# 07_MT7688AN_RF_Front_End.net
KiCad netlist of a schematic drawn in Altium Designer
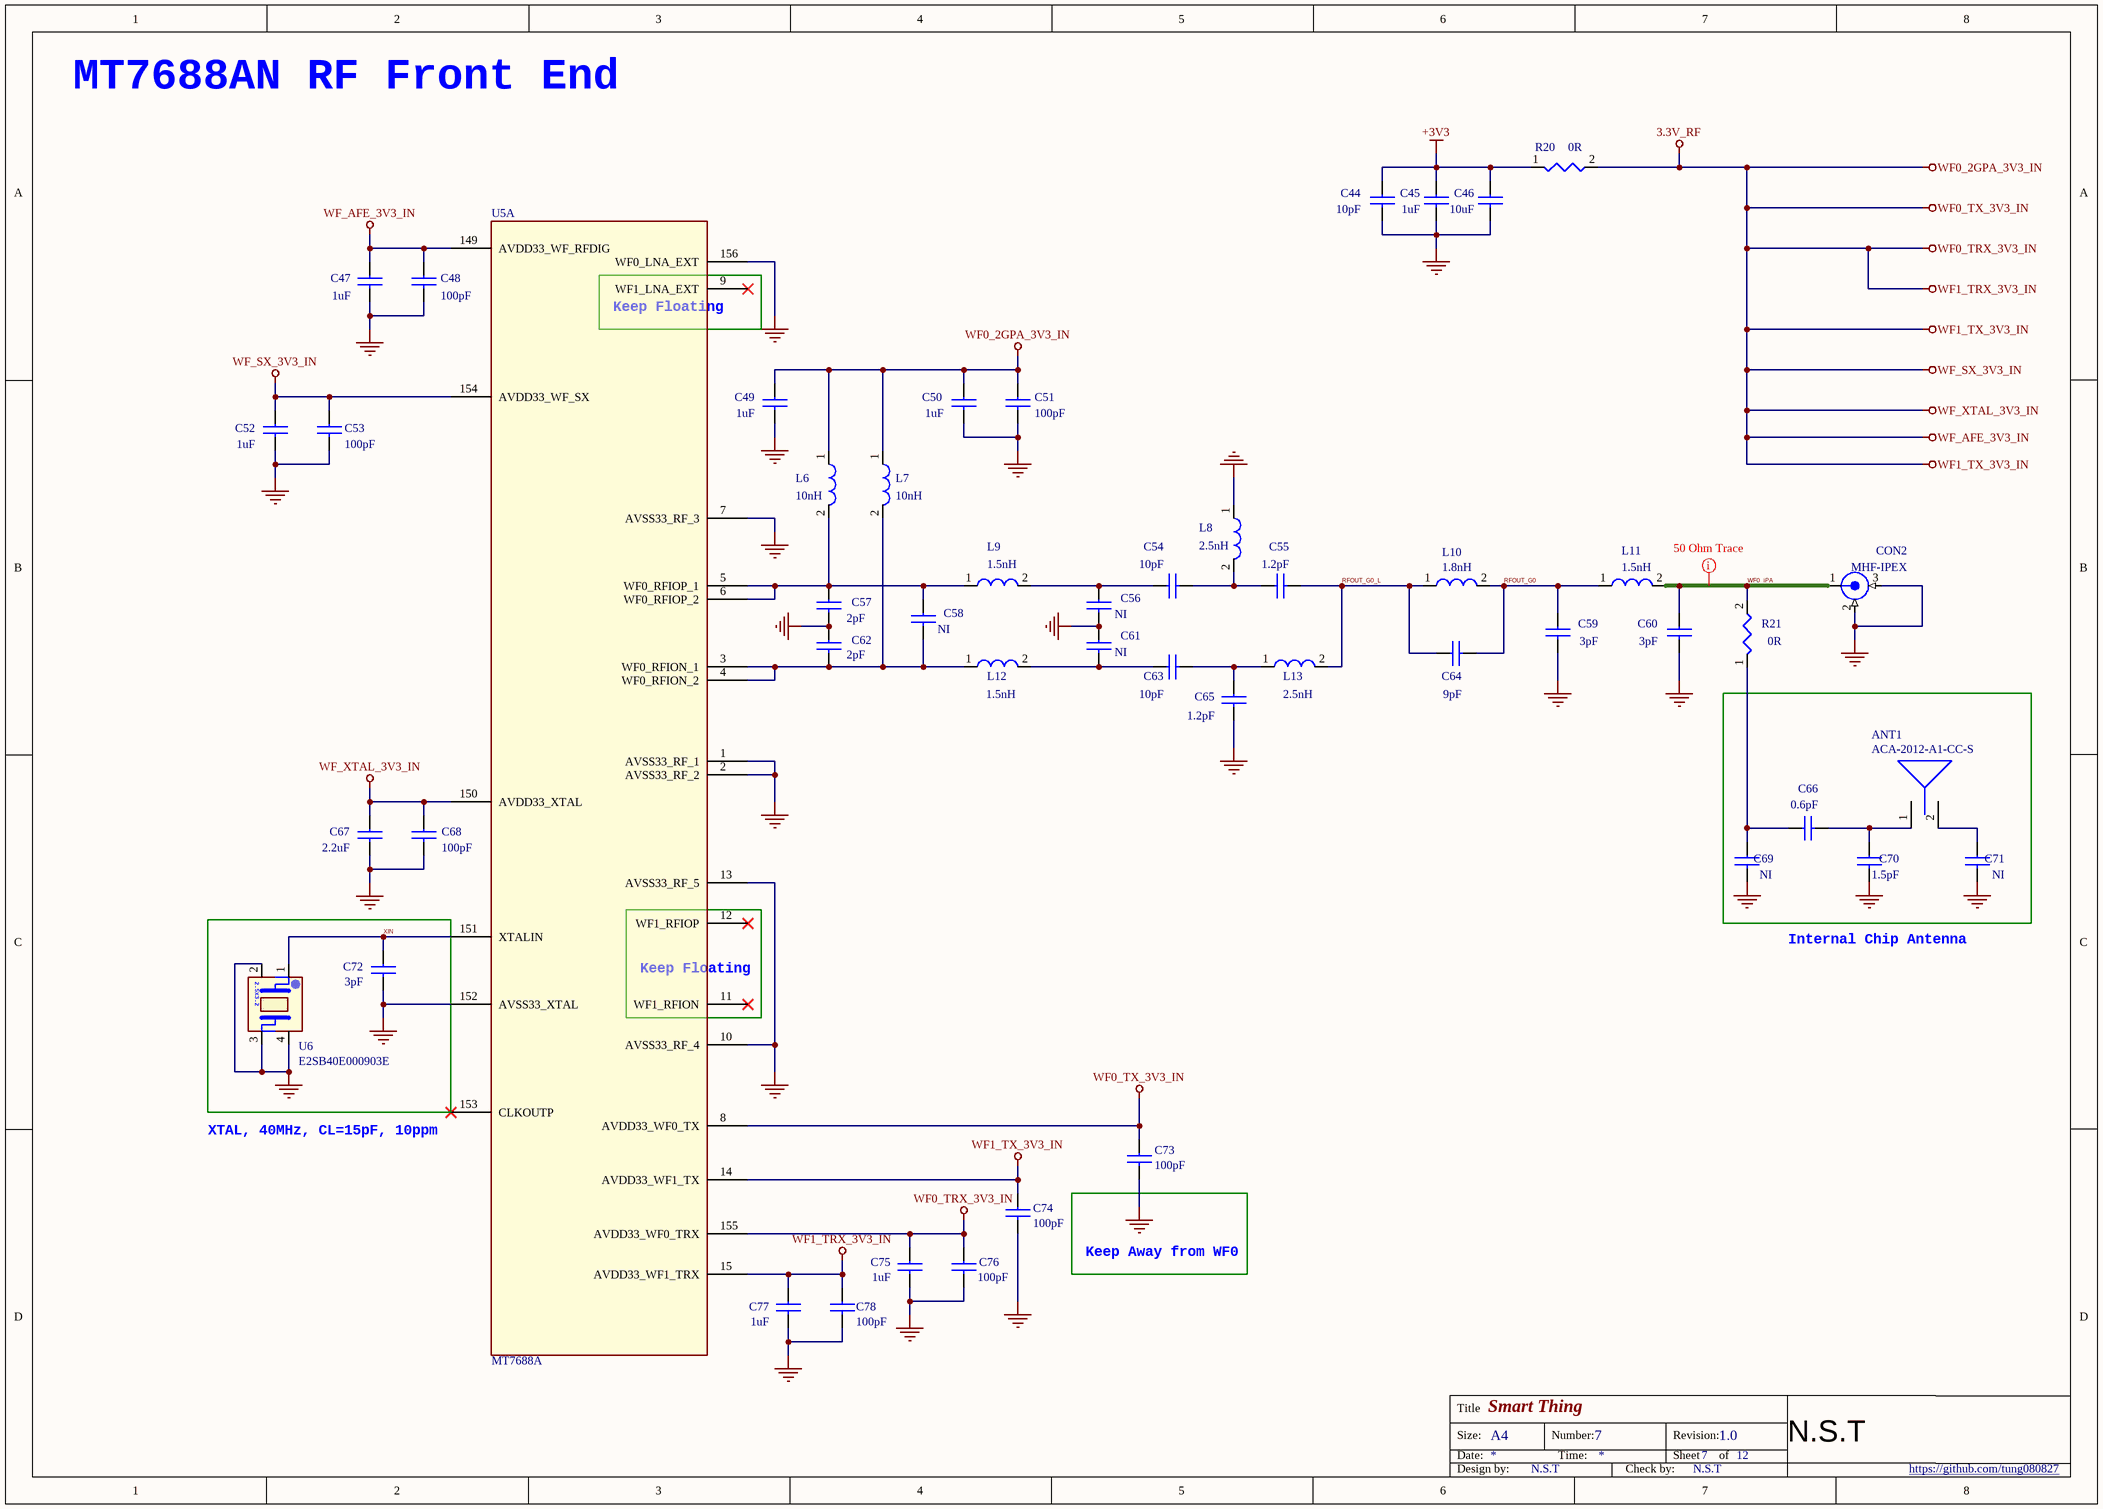
[diagram p0: 07. MT7688AN RF Front End.SchDoc]

(export (version "E")
  (design (tool "Eeschema 10.0.6"))
  (components
    (comp (ref "ANT1")
      (value "ACA-2012-A1-CC-S")
      (footprint "ACA-2012A")
      (libsource (lib "MT7688AN") (part "Antenna_2012"))
    )
    (comp (ref "C44")
      (value "10pF")
      (footprint "CAPC1005X60X30NL05T10")
      (libsource (lib "MT7688AN") (part "CAP NP"))
    )
    (comp (ref "C45")
      (value "1uF")
      (footprint "CAPC1608X90X35NL10T15")
      (libsource (lib "MT7688AN") (part "CAP NP"))
    )
    (comp (ref "C46")
      (value "10uF")
      (footprint "CAPC1608X90X35NL10T15")
      (libsource (lib "MT7688AN") (part "CAP NP"))
    )
    (comp (ref "C47")
      (value "1uF")
      (footprint "CAPC1608X90X35NL10T15")
      (libsource (lib "MT7688AN") (part "CAP NP"))
    )
    (comp (ref "C48")
      (value "100pF")
      (footprint "CAPC1005X60X30NL05T10")
      (libsource (lib "MT7688AN") (part "CAP NP"))
    )
    (comp (ref "C49")
      (value "1uF")
      (footprint "CAPC1005X60X30NL05T10")
      (libsource (lib "MT7688AN") (part "CAP NP"))
    )
    (comp (ref "C50")
      (value "1uF")
      (footprint "CAPC1005X60X30NL05T10")
      (libsource (lib "MT7688AN") (part "CAP NP"))
    )
    (comp (ref "C51")
      (value "100pF")
      (footprint "CAPC1005X60X30NL05T10")
      (libsource (lib "MT7688AN") (part "CAP NP"))
    )
    (comp (ref "C52")
      (value "1uF")
      (footprint "CAPC1608X90X35NL10T15")
      (libsource (lib "MT7688AN") (part "CAP NP"))
    )
    (comp (ref "C53")
      (value "100pF")
      (footprint "CAPC1005X60X30NL05T10")
      (libsource (lib "MT7688AN") (part "CAP NP"))
    )
    (comp (ref "C54")
      (value "10pF")
      (footprint "CAPC1005X60X30NL05T10")
      (libsource (lib "MT7688AN") (part "CAP NP"))
    )
    (comp (ref "C55")
      (value "1.2pF")
      (footprint "CAPC1005X60X30NL05T10")
      (libsource (lib "MT7688AN") (part "CAP NP"))
    )
    (comp (ref "C56")
      (value "NI")
      (footprint "CAPC1005X60X30NL05T10")
      (libsource (lib "MT7688AN") (part "CAP NP"))
    )
    (comp (ref "C57")
      (value "2pF")
      (footprint "CAPC1005X60X30NL05T10")
      (libsource (lib "MT7688AN") (part "CAP NP"))
    )
    (comp (ref "C58")
      (value "NI")
      (footprint "CAPC1005X60X30NL05T10")
      (libsource (lib "MT7688AN") (part "CAP NP"))
    )
    (comp (ref "C59")
      (value "3pF")
      (footprint "CAPC1005X60X30NL05T10")
      (libsource (lib "MT7688AN") (part "CAP NP"))
    )
    (comp (ref "C60")
      (value "3pF")
      (footprint "CAPC1005X60X30NL05T10")
      (libsource (lib "MT7688AN") (part "CAP NP"))
    )
    (comp (ref "C61")
      (value "NI")
      (footprint "CAPC1005X60X30NL05T10")
      (libsource (lib "MT7688AN") (part "CAP NP"))
    )
    (comp (ref "C62")
      (value "2pF")
      (footprint "CAPC1005X60X30NL05T10")
      (libsource (lib "MT7688AN") (part "CAP NP"))
    )
    (comp (ref "C63")
      (value "10pF")
      (footprint "CAPC1005X60X30NL05T10")
      (libsource (lib "MT7688AN") (part "CAP NP"))
    )
    (comp (ref "C64")
      (value "9pF")
      (footprint "CAPC1005X60X30NL05T10")
      (libsource (lib "MT7688AN") (part "CAP NP"))
    )
    (comp (ref "C65")
      (value "1.2pF")
      (footprint "CAPC1005X60X30NL05T10")
      (libsource (lib "MT7688AN") (part "CAP NP"))
    )
    (comp (ref "C66")
      (value "0.6pF")
      (footprint "CAPC1005X60X30NL05T10")
      (libsource (lib "MT7688AN") (part "CAP NP"))
    )
    (comp (ref "C67")
      (value "2.2uF")
      (footprint "CAPC1608X90X35NL10T15")
      (libsource (lib "MT7688AN") (part "CAP NP"))
    )
    (comp (ref "C68")
      (value "100pF")
      (footprint "CAPC1005X60X30NL05T10")
      (libsource (lib "MT7688AN") (part "CAP NP"))
    )
    (comp (ref "C69")
      (value "NI")
      (footprint "CAPC1005X60X30NL05T10")
      (libsource (lib "MT7688AN") (part "CAP NP"))
    )
    (comp (ref "C70")
      (value "1.5pF")
      (footprint "CAPC1005X60X30NL05T10")
      (libsource (lib "MT7688AN") (part "CAP NP"))
    )
    (comp (ref "C71")
      (value "NI")
      (footprint "CAPC1005X60X30NL05T10")
      (libsource (lib "MT7688AN") (part "CAP NP"))
    )
    (comp (ref "C72")
      (value "3pF")
      (footprint "CAPC1005X60X30NL05T10")
      (libsource (lib "MT7688AN") (part "CAP NP"))
    )
    (comp (ref "C73")
      (value "100pF")
      (footprint "CAPC1005X60X30NL05T10")
      (libsource (lib "MT7688AN") (part "CAP NP"))
    )
    (comp (ref "C74")
      (value "100pF")
      (footprint "CAPC1005X60X30NL05T10")
      (libsource (lib "MT7688AN") (part "CAP NP"))
    )
    (comp (ref "C75")
      (value "1uF")
      (footprint "CAPC1608X90X35NL10T15")
      (libsource (lib "MT7688AN") (part "CAP NP"))
    )
    (comp (ref "C76")
      (value "100pF")
      (footprint "CAPC1005X60X30NL05T10")
      (libsource (lib "MT7688AN") (part "CAP NP"))
    )
    (comp (ref "C77")
      (value "1uF")
      (footprint "CAPC1608X90X35NL10T15")
      (libsource (lib "MT7688AN") (part "CAP NP"))
    )
    (comp (ref "C78")
      (value "100pF")
      (footprint "CAPC1005X60X30NL05T10")
      (libsource (lib "MT7688AN") (part "CAP NP"))
    )
    (comp (ref "CON2")
      (value "MHF-IPEX")
      (footprint "I-PEX CON")
      (libsource (lib "MT7688AN") (part "SMA/UFLR"))
    )
    (comp (ref "L6")
      (value "10nH")
      (footprint "CAPC1005X60X30NL05T10")
      (libsource (lib "MT7688AN") (part "L/0402"))
    )
    (comp (ref "L7")
      (value "10nH")
      (footprint "CAPC1005X60X30NL05T10")
      (libsource (lib "MT7688AN") (part "L/0402"))
    )
    (comp (ref "L8")
      (value "2.5nH")
      (footprint "CAPC1005X60X30NL05T10")
      (libsource (lib "MT7688AN") (part "L/0402"))
    )
    (comp (ref "L9")
      (value "1.5nH")
      (footprint "CAPC1005X60X30NL05T10")
      (description "LQP03TN1N5B02D")
      (libsource (lib "MT7688AN") (part "L/0402"))
    )
    (comp (ref "L10")
      (value "1.8nH")
      (footprint "CAPC1005X60X30NL05T10")
      (libsource (lib "MT7688AN") (part "L/0402"))
    )
    (comp (ref "L11")
      (value "1.5nH")
      (footprint "CAPC1005X60X30NL05T10")
      (description "LQP03TN1N5B02D")
      (libsource (lib "MT7688AN") (part "L/0402"))
    )
    (comp (ref "L12")
      (value "1.5nH")
      (footprint "CAPC1005X60X30NL05T10")
      (description "LQP03TN1N5B02D")
      (libsource (lib "MT7688AN") (part "L/0402"))
    )
    (comp (ref "L13")
      (value "2.5nH")
      (footprint "CAPC1005X60X30NL05T10")
      (libsource (lib "MT7688AN") (part "L/0402"))
    )
    (comp (ref "R20")
      (value "0R")
      (footprint "RESC1609X50X30LL10T20")
      (libsource (lib "MT7688AN") (part "RES/0402_3"))
    )
    (comp (ref "R21")
      (value "0R")
      (footprint "RESC1005X40X25NL05T05")
      (libsource (lib "MT7688AN") (part "RES/0402_3"))
    )
    (comp (ref "U5")
      (value "MT7688A")
      (footprint "MT7628AN12X12")
      (libsource (lib "MT7688AN") (part "MT7620N-n_26"))
    )
    (comp (ref "U6")
      (value "E2SB40E000903E")
      (footprint "XTAL 2520")
      (description "XTAL, 40MHz, CL=15pF, 10ppm, -30~+85C")
      (libsource (lib "MT7688AN") (part "XTAL_3.2x2.5"))
    )
  )
  (nets
    (net (code "1") (name "+3V3") (class "Default")
      (node (ref "C44") (pin "1") (pinfunction "1_1") (pintype "passive"))
      (node (ref "C45") (pin "1") (pinfunction "1_1") (pintype "passive"))
      (node (ref "C46") (pin "1") (pinfunction "1_1") (pintype "passive"))
      (node (ref "R20") (pin "1") (pinfunction "1_1") (pintype "passive"))
    )
    (net (code "2") (name "/RFOUT_G0") (class "Default")
      (node (ref "C59") (pin "1") (pinfunction "1_1") (pintype "passive"))
      (node (ref "C64") (pin "2") (pinfunction "2_2") (pintype "passive"))
      (node (ref "L10") (pin "2") (pinfunction "2_2") (pintype "passive"))
      (node (ref "L11") (pin "1") (pinfunction "1_1") (pintype "passive"))
    )
    (net (code "3") (name "/RFOUT_G0_L") (class "Default")
      (node (ref "C55") (pin "2") (pinfunction "2_2") (pintype "passive"))
      (node (ref "C64") (pin "1") (pinfunction "1_1") (pintype "passive"))
      (node (ref "L10") (pin "1") (pinfunction "1_1") (pintype "passive"))
      (node (ref "L13") (pin "2") (pinfunction "2_2") (pintype "passive"))
    )
    (net (code "4") (name "/WF0_iPA") (class "Default")
      (node (ref "C60") (pin "1") (pinfunction "1_1") (pintype "passive"))
      (node (ref "CON2") (pin "1") (pinfunction "1_1") (pintype "passive"))
      (node (ref "L11") (pin "2") (pinfunction "2_2") (pintype "passive"))
      (node (ref "R21") (pin "2") (pinfunction "2_2") (pintype "passive"))
    )
    (net (code "5") (name "/XIN") (class "Default")
      (node (ref "C72") (pin "1") (pinfunction "1_1") (pintype "passive"))
      (node (ref "U5") (pin "151") (pinfunction "XTALIN_151") (pintype "passive"))
      (node (ref "U6") (pin "1") (pinfunction "X1_1") (pintype "passive"))
    )
    (net (code "6") (name "3.3V_RF") (class "Default")
      (node (ref "C47") (pin "1") (pinfunction "1_1") (pintype "passive"))
      (node (ref "C48") (pin "1") (pinfunction "1_1") (pintype "passive"))
      (node (ref "C49") (pin "1") (pinfunction "1_1") (pintype "passive"))
      (node (ref "C50") (pin "1") (pinfunction "1_1") (pintype "passive"))
      (node (ref "C51") (pin "1") (pinfunction "1_1") (pintype "passive"))
      (node (ref "C52") (pin "1") (pinfunction "1_1") (pintype "passive"))
      (node (ref "C53") (pin "1") (pinfunction "1_1") (pintype "passive"))
      (node (ref "C67") (pin "1") (pinfunction "1_1") (pintype "passive"))
      (node (ref "C68") (pin "1") (pinfunction "1_1") (pintype "passive"))
      (node (ref "C73") (pin "1") (pinfunction "1_1") (pintype "passive"))
      (node (ref "C74") (pin "1") (pinfunction "1_1") (pintype "passive"))
      (node (ref "C75") (pin "1") (pinfunction "1_1") (pintype "passive"))
      (node (ref "C76") (pin "1") (pinfunction "1_1") (pintype "passive"))
      (node (ref "C77") (pin "1") (pinfunction "1_1") (pintype "passive"))
      (node (ref "C78") (pin "1") (pinfunction "1_1") (pintype "passive"))
      (node (ref "L6") (pin "1") (pinfunction "1_1") (pintype "passive"))
      (node (ref "L7") (pin "1") (pinfunction "1_1") (pintype "passive"))
      (node (ref "R20") (pin "2") (pinfunction "2_2") (pintype "passive"))
      (node (ref "U5") (pin "14") (pinfunction "AVDD33_WF1_TX_14") (pintype "power_in"))
      (node (ref "U5") (pin "149") (pinfunction "AVDD33_WF_RFDIG_149") (pintype "power_in"))
      (node (ref "U5") (pin "15") (pinfunction "AVDD33_WF1_TRX_15") (pintype "power_in"))
      (node (ref "U5") (pin "150") (pinfunction "AVDD33_XTAL_150") (pintype "power_in"))
      (node (ref "U5") (pin "154") (pinfunction "AVDD33_WF_SX_154") (pintype "power_in"))
      (node (ref "U5") (pin "155") (pinfunction "AVDD33_WF0_TRX_155") (pintype "power_in"))
      (node (ref "U5") (pin "8") (pinfunction "AVDD33_WF0_TX_8") (pintype "power_in"))
    )
    (net (code "7") (name "GND") (class "Default")
      (node (ref "C44") (pin "2") (pinfunction "2_2") (pintype "passive"))
      (node (ref "C45") (pin "2") (pinfunction "2_2") (pintype "passive"))
      (node (ref "C46") (pin "2") (pinfunction "2_2") (pintype "passive"))
      (node (ref "C47") (pin "2") (pinfunction "2_2") (pintype "passive"))
      (node (ref "C48") (pin "2") (pinfunction "2_2") (pintype "passive"))
      (node (ref "C49") (pin "2") (pinfunction "2_2") (pintype "passive"))
      (node (ref "C50") (pin "2") (pinfunction "2_2") (pintype "passive"))
      (node (ref "C51") (pin "2") (pinfunction "2_2") (pintype "passive"))
      (node (ref "C52") (pin "2") (pinfunction "2_2") (pintype "passive"))
      (node (ref "C53") (pin "2") (pinfunction "2_2") (pintype "passive"))
      (node (ref "C56") (pin "2") (pinfunction "2_2") (pintype "passive"))
      (node (ref "C57") (pin "2") (pinfunction "2_2") (pintype "passive"))
      (node (ref "C59") (pin "2") (pinfunction "2_2") (pintype "passive"))
      (node (ref "C60") (pin "2") (pinfunction "2_2") (pintype "passive"))
      (node (ref "C61") (pin "1") (pinfunction "1_1") (pintype "passive"))
      (node (ref "C62") (pin "1") (pinfunction "1_1") (pintype "passive"))
      (node (ref "C65") (pin "2") (pinfunction "2_2") (pintype "passive"))
      (node (ref "C67") (pin "2") (pinfunction "2_2") (pintype "passive"))
      (node (ref "C68") (pin "2") (pinfunction "2_2") (pintype "passive"))
      (node (ref "C69") (pin "2") (pinfunction "2_2") (pintype "passive"))
      (node (ref "C70") (pin "2") (pinfunction "2_2") (pintype "passive"))
      (node (ref "C71") (pin "2") (pinfunction "2_2") (pintype "passive"))
      (node (ref "C72") (pin "2") (pinfunction "2_2") (pintype "passive"))
      (node (ref "C73") (pin "2") (pinfunction "2_2") (pintype "passive"))
      (node (ref "C74") (pin "2") (pinfunction "2_2") (pintype "passive"))
      (node (ref "C75") (pin "2") (pinfunction "2_2") (pintype "passive"))
      (node (ref "C76") (pin "2") (pinfunction "2_2") (pintype "passive"))
      (node (ref "C77") (pin "2") (pinfunction "2_2") (pintype "passive"))
      (node (ref "C78") (pin "2") (pinfunction "2_2") (pintype "passive"))
      (node (ref "CON2") (pin "2") (pinfunction "2_2") (pintype "input"))
      (node (ref "CON2") (pin "3") (pinfunction "GNDA_3") (pintype "input"))
      (node (ref "L8") (pin "1") (pinfunction "1_1") (pintype "passive"))
      (node (ref "U5") (pin "1") (pinfunction "AVSS33_RF_1_1") (pintype "passive"))
      (node (ref "U5") (pin "10") (pinfunction "AVSS33_RF_4_10") (pintype "passive"))
      (node (ref "U5") (pin "13") (pinfunction "AVSS33_RF_5_13") (pintype "passive"))
      (node (ref "U5") (pin "152") (pinfunction "AVSS33_XTAL_152") (pintype "passive"))
      (node (ref "U5") (pin "156") (pinfunction "WF0_LNA_EXT_156") (pintype "passive"))
      (node (ref "U5") (pin "2") (pinfunction "AVSS33_RF_2_2") (pintype "passive"))
      (node (ref "U5") (pin "7") (pinfunction "AVSS33_RF_3_7") (pintype "passive"))
      (node (ref "U6") (pin "2") (pinfunction "NC_2") (pintype "passive"))
      (node (ref "U6") (pin "3") (pinfunction "X2_3") (pintype "passive"))
      (node (ref "U6") (pin "4") (pinfunction "NC_4") (pintype "passive"))
    )
    (net (code "8") (name "Net-(ANT1-IN)") (class "Default")
      (node (ref "ANT1") (pin "1") (pinfunction "IN_1") (pintype "passive"))
      (node (ref "C66") (pin "2") (pinfunction "2_2") (pintype "passive"))
      (node (ref "C70") (pin "1") (pinfunction "1_1") (pintype "passive"))
    )
    (net (code "9") (name "Net-(ANT1-OUT)") (class "Default")
      (node (ref "ANT1") (pin "2") (pinfunction "OUT_2") (pintype "passive"))
      (node (ref "C71") (pin "1") (pinfunction "1_1") (pintype "passive"))
    )
    (net (code "10") (name "Net-(C54-Pad1)") (class "Default")
      (node (ref "C54") (pin "1") (pinfunction "1_1") (pintype "passive"))
      (node (ref "C56") (pin "1") (pinfunction "1_1") (pintype "passive"))
      (node (ref "L9") (pin "2") (pinfunction "2_2") (pintype "passive"))
    )
    (net (code "11") (name "Net-(C54-Pad2)") (class "Default")
      (node (ref "C54") (pin "2") (pinfunction "2_2") (pintype "passive"))
      (node (ref "C55") (pin "1") (pinfunction "1_1") (pintype "passive"))
      (node (ref "L8") (pin "2") (pinfunction "2_2") (pintype "passive"))
    )
    (net (code "12") (name "Net-(C61-Pad2)") (class "Default")
      (node (ref "C61") (pin "2") (pinfunction "2_2") (pintype "passive"))
      (node (ref "C63") (pin "1") (pinfunction "1_1") (pintype "passive"))
      (node (ref "L12") (pin "2") (pinfunction "2_2") (pintype "passive"))
    )
    (net (code "13") (name "Net-(C63-Pad2)") (class "Default")
      (node (ref "C63") (pin "2") (pinfunction "2_2") (pintype "passive"))
      (node (ref "C65") (pin "1") (pinfunction "1_1") (pintype "passive"))
      (node (ref "L13") (pin "1") (pinfunction "1_1") (pintype "passive"))
    )
    (net (code "14") (name "Net-(C66-Pad1)") (class "Default")
      (node (ref "C66") (pin "1") (pinfunction "1_1") (pintype "passive"))
      (node (ref "C69") (pin "1") (pinfunction "1_1") (pintype "passive"))
      (node (ref "R21") (pin "1") (pinfunction "1_1") (pintype "passive"))
    )
    (net (code "15") (name "Net-(U5A-WF0_RFION_1)") (class "Default")
      (node (ref "C58") (pin "2") (pinfunction "2_2") (pintype "passive"))
      (node (ref "C62") (pin "2") (pinfunction "2_2") (pintype "passive"))
      (node (ref "L12") (pin "1") (pinfunction "1_1") (pintype "passive"))
      (node (ref "L7") (pin "2") (pinfunction "2_2") (pintype "passive"))
      (node (ref "U5") (pin "3") (pinfunction "WF0_RFION_1_3") (pintype "passive"))
      (node (ref "U5") (pin "4") (pinfunction "WF0_RFION_2_4") (pintype "passive"))
    )
    (net (code "16") (name "Net-(U5A-WF0_RFIOP_1)") (class "Default")
      (node (ref "C57") (pin "1") (pinfunction "1_1") (pintype "passive"))
      (node (ref "C58") (pin "1") (pinfunction "1_1") (pintype "passive"))
      (node (ref "L6") (pin "2") (pinfunction "2_2") (pintype "passive"))
      (node (ref "L9") (pin "1") (pinfunction "1_1") (pintype "passive"))
      (node (ref "U5") (pin "5") (pinfunction "WF0_RFIOP_1_5") (pintype "passive"))
      (node (ref "U5") (pin "6") (pinfunction "WF0_RFIOP_2_6") (pintype "passive"))
    )
    (net (code "17") (name "unconnected-(U5A-CLKOUTP-Pad153)") (class "Default")
      (node (ref "U5") (pin "153") (pinfunction "CLKOUTP_153") (pintype "passive+no_connect"))
    )
    (net (code "18") (name "unconnected-(U5A-WF1_LNA_EXT-Pad9)") (class "Default")
      (node (ref "U5") (pin "9") (pinfunction "WF1_LNA_EXT_9") (pintype "passive+no_connect"))
    )
    (net (code "19") (name "unconnected-(U5A-WF1_RFION-Pad11)") (class "Default")
      (node (ref "U5") (pin "11") (pinfunction "WF1_RFION_11") (pintype "passive+no_connect"))
    )
    (net (code "20") (name "unconnected-(U5A-WF1_RFIOP-Pad12)") (class "Default")
      (node (ref "U5") (pin "12") (pinfunction "WF1_RFIOP_12") (pintype "passive+no_connect"))
    )
  )
)
